# DSO_IO.net
KiCad netlist of a schematic drawn in Altium Designer
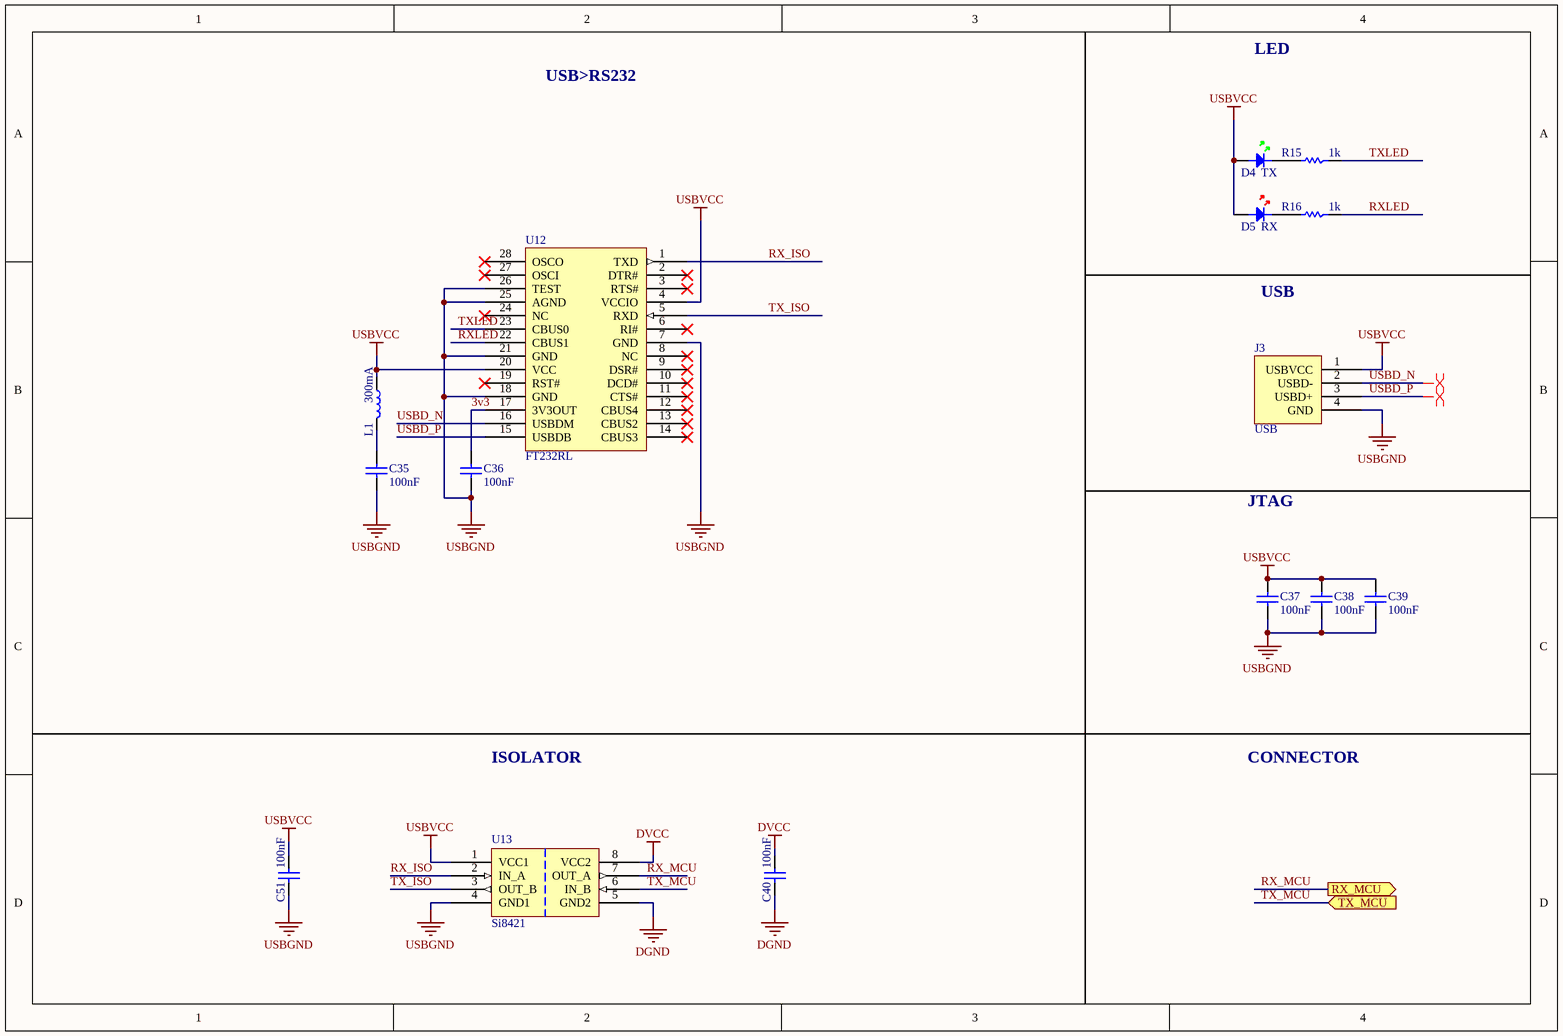
[diagram p0: DSO_IO.SchDoc]

(export (version "E")
  (design (tool "Eeschema 10.0.6"))
  (components
    (comp (ref "C35")
      (value "100nF")
      (footprint "0805C")
      (description "Capacitor")
      (fields (field (name "REVIEWED BY") "RM - 2018/08/05"))
      (libsource (lib "DSO") (part "C"))
    )
    (comp (ref "C36")
      (value "100nF")
      (footprint "0805C")
      (description "Capacitor")
      (fields (field (name "REVIEWED BY") "RM - 2018/08/05"))
      (libsource (lib "DSO") (part "C"))
    )
    (comp (ref "C37")
      (value "100nF")
      (footprint "0805C")
      (description "Capacitor")
      (fields (field (name "REVIEWED BY") "RM - 2018/08/05"))
      (libsource (lib "DSO") (part "C"))
    )
    (comp (ref "C38")
      (value "100nF")
      (footprint "0805C")
      (description "Capacitor")
      (fields (field (name "REVIEWED BY") "RM - 2018/08/05"))
      (libsource (lib "DSO") (part "C"))
    )
    (comp (ref "C39")
      (value "100nF")
      (footprint "0805C")
      (description "Capacitor")
      (fields (field (name "REVIEWED BY") "RM - 2018/08/05"))
      (libsource (lib "DSO") (part "C"))
    )
    (comp (ref "C40")
      (value "100nF")
      (footprint "0805C")
      (description "Capacitor")
      (fields (field (name "REVIEWED BY") "RM - 2018/08/05"))
      (libsource (lib "DSO") (part "C"))
    )
    (comp (ref "C51")
      (value "100nF")
      (footprint "0805C")
      (description "Capacitor")
      (fields (field (name "REVIEWED BY") "RM - 2018/08/05"))
      (libsource (lib "DSO") (part "C"))
    )
    (comp (ref "D4")
      (value "TX")
      (footprint "0805D-GREEN")
      (description "Light Emitting Diode")
      (fields (field (name "REVIEWED BY") "RM - 2018/08/05"))
      (libsource (lib "DSO") (part "LED GREEN"))
    )
    (comp (ref "D5")
      (value "RX")
      (footprint "0805D-RED")
      (description "Light Emitting Diode")
      (fields (field (name "REVIEWED BY") "RM - 2018/08/05"))
      (libsource (lib "DSO") (part "LED RED"))
    )
    (comp (ref "J3")
      (value "USB")
      (footprint "USBPLUG")
      (description "USB B Type Connector")
      (fields (field (name "REVIEWED BY") "RM - 2018/08/05"))
      (libsource (lib "DSO") (part "USBPLUG"))
    )
    (comp (ref "L1")
      (value "300mA")
      (footprint "0805")
      (description "Inductor")
      (fields (field (name "REVIEWED BY") "RM - 2018/08/05"))
      (libsource (lib "DSO") (part "I"))
    )
    (comp (ref "R15")
      (value "1k")
      (footprint "0805")
      (description "Resistor")
      (fields (field (name "REVIEWED BY") "RM - 2018/08/05"))
      (libsource (lib "DSO") (part "R"))
    )
    (comp (ref "R16")
      (value "1k")
      (footprint "0805")
      (description "Resistor")
      (fields (field (name "REVIEWED BY") "RM - 2018/08/05"))
      (libsource (lib "DSO") (part "R"))
    )
    (comp (ref "U12")
      (value "FT232RL")
      (footprint "SSOP-28")
      (description "USB to Serial bridge")
      (fields (field (name "REVIEWED BY") "RM - 2018/08/05"))
      (libsource (lib "DSO") (part "FT232RL"))
    )
    (comp (ref "U13")
      (value "Si8421")
      (footprint "SOIC-8")
      (description "Dual Channel Digital Isolator Both Ways")
      (fields (field (name "REVIEWED BY") "RM - 2018/08/05"))
      (libsource (lib "DSO") (part "Si8421"))
    )
  )
  (nets
    (net (code "1") (name "/3v3") (class "Default")
      (node (ref "C36") (pin "1") (pinfunction "1_1") (pintype "passive"))
      (node (ref "U12") (pin "17") (pinfunction "3V3OUT_17") (pintype "passive"))
    )
    (net (code "2") (name "/RXLED") (class "Default")
      (node (ref "R16") (pin "1") (pintype "passive"))
      (node (ref "U12") (pin "22") (pinfunction "CBUS1_22") (pintype "passive"))
    )
    (net (code "3") (name "/RX_ISO") (class "Default")
      (node (ref "U12") (pin "1") (pinfunction "TXD_1") (pintype "output"))
      (node (ref "U13") (pin "2") (pinfunction "IN_A_2") (pintype "input"))
    )
    (net (code "4") (name "/RX_MCU") (class "Default")
      (node (ref "U13") (pin "7") (pinfunction "OUT_A_7") (pintype "output"))
    )
    (net (code "5") (name "/TXLED") (class "Default")
      (node (ref "R15") (pin "1") (pintype "passive"))
      (node (ref "U12") (pin "23") (pinfunction "CBUS0_23") (pintype "passive"))
    )
    (net (code "6") (name "/TX_ISO") (class "Default")
      (node (ref "U12") (pin "5") (pinfunction "RXD_5") (pintype "input"))
      (node (ref "U13") (pin "3") (pinfunction "OUT_B_3") (pintype "output"))
    )
    (net (code "7") (name "/TX_MCU") (class "Default")
      (node (ref "U13") (pin "6") (pinfunction "IN_B_6") (pintype "input"))
    )
    (net (code "8") (name "/USBD_N") (class "Default")
      (node (ref "J3") (pin "2") (pinfunction "USBD-_2") (pintype "passive"))
      (node (ref "U12") (pin "16") (pinfunction "USBDM_16") (pintype "passive"))
    )
    (net (code "9") (name "/USBD_P") (class "Default")
      (node (ref "J3") (pin "3") (pinfunction "USBD+_3") (pintype "passive"))
      (node (ref "U12") (pin "15") (pinfunction "USBDB_15") (pintype "passive"))
    )
    (net (code "10") (name "DGND") (class "Default")
      (node (ref "C40") (pin "2") (pinfunction "2_2") (pintype "passive"))
      (node (ref "U13") (pin "5") (pinfunction "GND2_5") (pintype "passive"))
    )
    (net (code "11") (name "DVCC") (class "Default")
      (node (ref "C40") (pin "1") (pinfunction "1_1") (pintype "passive"))
      (node (ref "U13") (pin "8") (pinfunction "VCC2_8") (pintype "passive"))
    )
    (net (code "12") (name "Net-(C35-Pad1)") (class "Default")
      (node (ref "C35") (pin "1") (pinfunction "1_1") (pintype "passive"))
      (node (ref "L1") (pin "2") (pinfunction "2_2") (pintype "passive"))
    )
    (net (code "13") (name "Net-(D4-PadK)") (class "Default")
      (node (ref "D4") (pin "K") (pinfunction "K_K") (pintype "passive"))
      (node (ref "R15") (pin "2") (pintype "passive"))
    )
    (net (code "14") (name "Net-(D5-PadK)") (class "Default")
      (node (ref "D5") (pin "K") (pinfunction "K_K") (pintype "passive"))
      (node (ref "R16") (pin "2") (pintype "passive"))
    )
    (net (code "15") (name "USBGND") (class "Default")
      (node (ref "C35") (pin "2") (pinfunction "2_2") (pintype "passive"))
      (node (ref "C36") (pin "2") (pinfunction "2_2") (pintype "passive"))
      (node (ref "C37") (pin "2") (pinfunction "2_2") (pintype "passive"))
      (node (ref "C38") (pin "2") (pinfunction "2_2") (pintype "passive"))
      (node (ref "C39") (pin "2") (pinfunction "2_2") (pintype "passive"))
      (node (ref "C51") (pin "2") (pinfunction "2_2") (pintype "passive"))
      (node (ref "J3") (pin "4") (pinfunction "GND_4") (pintype "passive"))
      (node (ref "U12") (pin "18") (pinfunction "GND_18") (pintype "passive"))
      (node (ref "U12") (pin "21") (pinfunction "GND_21") (pintype "passive"))
      (node (ref "U12") (pin "25") (pinfunction "AGND_25") (pintype "passive"))
      (node (ref "U12") (pin "26") (pinfunction "TEST_26") (pintype "passive"))
      (node (ref "U12") (pin "7") (pinfunction "GND_7") (pintype "passive"))
      (node (ref "U13") (pin "4") (pinfunction "GND1_4") (pintype "passive"))
    )
    (net (code "16") (name "USBVCC") (class "Default")
      (node (ref "C37") (pin "1") (pinfunction "1_1") (pintype "passive"))
      (node (ref "C38") (pin "1") (pinfunction "1_1") (pintype "passive"))
      (node (ref "C39") (pin "1") (pinfunction "1_1") (pintype "passive"))
      (node (ref "C51") (pin "1") (pinfunction "1_1") (pintype "passive"))
      (node (ref "D4") (pin "A") (pinfunction "A_A") (pintype "passive"))
      (node (ref "D5") (pin "A") (pinfunction "A_A") (pintype "passive"))
      (node (ref "J3") (pin "1") (pinfunction "USBVCC_1") (pintype "passive"))
      (node (ref "L1") (pin "1") (pinfunction "1_1") (pintype "passive"))
      (node (ref "U12") (pin "20") (pinfunction "VCC_20") (pintype "passive"))
      (node (ref "U12") (pin "4") (pinfunction "VCCIO_4") (pintype "passive"))
      (node (ref "U13") (pin "1") (pinfunction "VCC1_1") (pintype "passive"))
    )
    (net (code "17") (name "unconnected-(U12-CBUS2-Pad13)") (class "Default")
      (node (ref "U12") (pin "13") (pinfunction "CBUS2_13") (pintype "passive+no_connect"))
    )
    (net (code "18") (name "unconnected-(U12-CBUS3-Pad14)") (class "Default")
      (node (ref "U12") (pin "14") (pinfunction "CBUS3_14") (pintype "passive+no_connect"))
    )
    (net (code "19") (name "unconnected-(U12-CBUS4-Pad12)") (class "Default")
      (node (ref "U12") (pin "12") (pinfunction "CBUS4_12") (pintype "passive+no_connect"))
    )
    (net (code "20") (name "unconnected-(U12-CTS#-Pad11)") (class "Default")
      (node (ref "U12") (pin "11") (pinfunction "CTS#_11") (pintype "passive+no_connect"))
    )
    (net (code "21") (name "unconnected-(U12-DCD#-Pad10)") (class "Default")
      (node (ref "U12") (pin "10") (pinfunction "DCD#_10") (pintype "passive+no_connect"))
    )
    (net (code "22") (name "unconnected-(U12-DSR#-Pad9)") (class "Default")
      (node (ref "U12") (pin "9") (pinfunction "DSR#_9") (pintype "passive+no_connect"))
    )
    (net (code "23") (name "unconnected-(U12-DTR#-Pad2)") (class "Default")
      (node (ref "U12") (pin "2") (pinfunction "DTR#_2") (pintype "passive+no_connect"))
    )
    (net (code "24") (name "unconnected-(U12-NC-Pad8)") (class "Default")
      (node (ref "U12") (pin "8") (pinfunction "NC_8") (pintype "passive+no_connect"))
    )
    (net (code "25") (name "unconnected-(U12-NC-Pad24)") (class "Default")
      (node (ref "U12") (pin "24") (pinfunction "NC_24") (pintype "passive+no_connect"))
    )
    (net (code "26") (name "unconnected-(U12-OSCI-Pad27)") (class "Default")
      (node (ref "U12") (pin "27") (pinfunction "OSCI_27") (pintype "passive+no_connect"))
    )
    (net (code "27") (name "unconnected-(U12-OSCO-Pad28)") (class "Default")
      (node (ref "U12") (pin "28") (pinfunction "OSCO_28") (pintype "passive+no_connect"))
    )
    (net (code "28") (name "unconnected-(U12-RI#-Pad6)") (class "Default")
      (node (ref "U12") (pin "6") (pinfunction "RI#_6") (pintype "passive+no_connect"))
    )
    (net (code "29") (name "unconnected-(U12-RST#-Pad19)") (class "Default")
      (node (ref "U12") (pin "19") (pinfunction "RST#_19") (pintype "passive+no_connect"))
    )
    (net (code "30") (name "unconnected-(U12-RTS#-Pad3)") (class "Default")
      (node (ref "U12") (pin "3") (pinfunction "RTS#_3") (pintype "passive+no_connect"))
    )
  )
)
